# Sheet2.net
KiCad netlist of a schematic drawn in Altium Designer
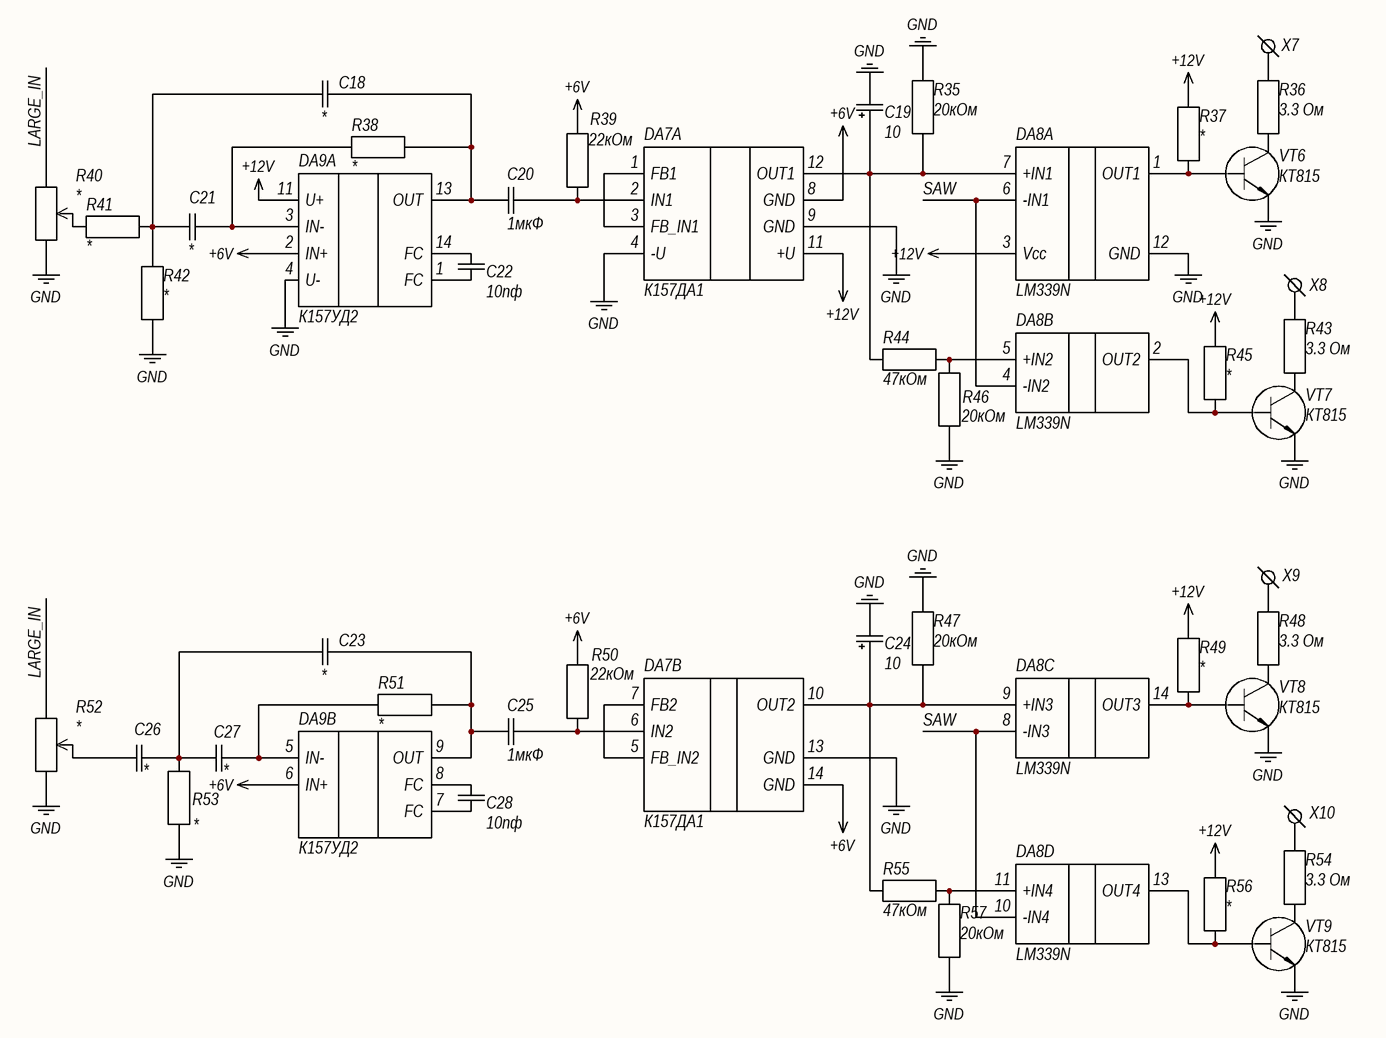
[diagram p0: Sheet2.SchDoc]

(export (version "E")
  (design (tool "Eeschema 10.0.6"))
  (components
    (comp (ref "C18") (value "*") (footprint "C 15mm") (libsource (lib "lib") (part "Capacitor")))
    (comp (ref "C19") (value "10") (footprint "C 3.5mm") (libsource (lib "lib") (part "Capacitor Pol")))
    (comp (ref "C20") (value "1мкФ") (footprint "C 10mm") (libsource (lib "lib") (part "Capacitor")))
    (comp (ref "C21") (value "*") (footprint "C 15mm") (libsource (lib "lib") (part "Capacitor")))
    (comp (ref "C22") (value "10пф") (footprint "C 10mm") (libsource (lib "lib") (part "Capacitor")))
    (comp (ref "C23") (value "*") (footprint "C 15mm") (libsource (lib "lib") (part "Capacitor")))
    (comp (ref "C24") (value "10") (footprint "C 3.5mm") (libsource (lib "lib") (part "Capacitor Pol")))
    (comp (ref "C25") (value "1мкФ") (footprint "C 10mm") (libsource (lib "lib") (part "Capacitor")))
    (comp (ref "C26") (value "*") (footprint "C 15mm") (libsource (lib "lib") (part "Capacitor")))
    (comp (ref "C27") (value "*") (footprint "C 15mm") (libsource (lib "lib") (part "Capacitor")))
    (comp (ref "C28") (value "10пф") (footprint "C 10mm") (libsource (lib "lib") (part "Capacitor")))
    (comp (ref "DA7") (value "К157ДА1") (footprint "14-LEAD DIP") (libsource (lib "lib") (part "К157ДА1")))
    (comp (ref "DA8") (value "LM339N") (footprint "14-LEAD DIP") (libsource (lib "lib") (part "LM339N")))
    (comp (ref "DA9") (value "К157УД2") (footprint "14-LEAD DIP") (libsource (lib "lib") (part "К157УД2")))
    (comp (ref "R35") (value "20кОм") (footprint "R 10mm") (libsource (lib "") (part "Resistor_1")))
    (comp (ref "R36") (value "3.3 Ом") (footprint "R 10mm") (libsource (lib "") (part "Resistor_1")))
    (comp (ref "R37") (value "*") (footprint "R 10mm") (libsource (lib "") (part "Resistor_1")))
    (comp (ref "R38") (value "*") (footprint "R 10mm") (libsource (lib "") (part "Resistor_2")))
    (comp (ref "R39") (value "22кОм") (footprint "R 10mm") (libsource (lib "") (part "Resistor_1")))
    (comp (ref "R40")
      (value "*")
      (footprint "OFF BOARD RESISTOR")
      (libsource (lib "lib") (part "ResistorVar"))
    )
    (comp (ref "R41") (value "*") (footprint "R 10mm") (libsource (lib "lib") (part "Resistor")))
    (comp (ref "R42") (value "*") (footprint "R 10mm") (libsource (lib "") (part "Resistor_1")))
    (comp (ref "R43") (value "3.3 Ом") (footprint "R 10mm") (libsource (lib "") (part "Resistor_1")))
    (comp (ref "R44") (value "47кОм") (footprint "R 10mm") (libsource (lib "lib") (part "Resistor")))
    (comp (ref "R45") (value "*") (footprint "R 10mm") (libsource (lib "") (part "Resistor_1")))
    (comp (ref "R46") (value "20кОм") (footprint "R 10mm") (libsource (lib "") (part "Resistor_1")))
    (comp (ref "R47") (value "20кОм") (footprint "R 10mm") (libsource (lib "") (part "Resistor_1")))
    (comp (ref "R48") (value "3.3 Ом") (footprint "R 10mm") (libsource (lib "") (part "Resistor_1")))
    (comp (ref "R49") (value "*") (footprint "R 10mm") (libsource (lib "") (part "Resistor_1")))
    (comp (ref "R50") (value "22кОм") (footprint "R 10mm") (libsource (lib "") (part "Resistor_1")))
    (comp (ref "R51") (value "*") (footprint "R 10mm") (libsource (lib "") (part "Resistor_2")))
    (comp (ref "R52")
      (value "*")
      (footprint "OFF BOARD RESISTOR")
      (libsource (lib "lib") (part "ResistorVar"))
    )
    (comp (ref "R53") (value "*") (footprint "R 10mm") (libsource (lib "") (part "Resistor_1")))
    (comp (ref "R54") (value "3.3 Ом") (footprint "R 10mm") (libsource (lib "") (part "Resistor_1")))
    (comp (ref "R55") (value "47кОм") (footprint "R 10mm") (libsource (lib "lib") (part "Resistor")))
    (comp (ref "R56") (value "*") (footprint "R 10mm") (libsource (lib "") (part "Resistor_1")))
    (comp (ref "R57") (value "20кОм") (footprint "R 10mm") (libsource (lib "") (part "Resistor_1")))
    (comp (ref "VT6")
      (value "КТ815")
      (footprint "KT-27")
      (description "Transistor")
      (libsource (lib "lib") (part "NPN"))
    )
    (comp (ref "VT7")
      (value "КТ815")
      (footprint "KT-27")
      (description "Transistor")
      (libsource (lib "lib") (part "NPN"))
    )
    (comp (ref "VT8")
      (value "КТ815")
      (footprint "KT-27")
      (description "Transistor")
      (libsource (lib "lib") (part "NPN"))
    )
    (comp (ref "VT9")
      (value "КТ815")
      (footprint "KT-27")
      (description "Transistor")
      (libsource (lib "lib") (part "NPN"))
    )
    (comp (ref "X7") (value "~") (footprint "TP 1,4mm") (libsource (lib "lib") (part "TP")))
    (comp (ref "X8") (value "~") (footprint "TP 1,4mm") (libsource (lib "lib") (part "TP")))
    (comp (ref "X9") (value "~") (footprint "TP 1,4mm") (libsource (lib "lib") (part "TP")))
    (comp (ref "X10") (value "~") (footprint "TP 1,4mm") (libsource (lib "lib") (part "TP")))
  )
  (nets
    (net (code "1") (name "+6V") (class "Default")
      (node (ref "DA7") (pin "14") (pinfunction "GND_14") (pintype "power_in"))
      (node (ref "DA7") (pin "8") (pinfunction "GND_8") (pintype "power_in"))
      (node (ref "DA9") (pin "2") (pinfunction "IN+_2") (pintype "power_in"))
      (node (ref "DA9") (pin "6") (pinfunction "IN+_6") (pintype "power_in"))
      (node (ref "R39") (pin "2") (pinfunction "2_2") (pintype "passive"))
      (node (ref "R50") (pin "2") (pinfunction "2_2") (pintype "passive"))
    )
    (net (code "2") (name "+12V") (class "Default")
      (node (ref "DA7") (pin "11") (pinfunction "+U_11") (pintype "power_in"))
      (node (ref "DA8") (pin "3") (pinfunction "Vcc_3") (pintype "power_in"))
      (node (ref "DA9") (pin "11") (pinfunction "U+_11") (pintype "power_in"))
      (node (ref "R37") (pin "2") (pinfunction "2_2") (pintype "passive"))
      (node (ref "R45") (pin "2") (pinfunction "2_2") (pintype "passive"))
      (node (ref "R49") (pin "2") (pinfunction "2_2") (pintype "passive"))
      (node (ref "R56") (pin "2") (pinfunction "2_2") (pintype "passive"))
    )
    (net (code "3") (name "/LARGE_IN") (class "Default")
      (node (ref "R40") (pin "1") (pinfunction "1_1") (pintype "passive"))
      (node (ref "R52") (pin "1") (pinfunction "1_1") (pintype "passive"))
    )
    (net (code "4") (name "/SAW") (class "Default")
      (node (ref "DA8") (pin "10") (pinfunction "-IN4_10") (pintype "power_in"))
      (node (ref "DA8") (pin "4") (pinfunction "-IN2_4") (pintype "power_in"))
      (node (ref "DA8") (pin "6") (pinfunction "-IN1_6") (pintype "power_in"))
      (node (ref "DA8") (pin "8") (pinfunction "-IN3_8") (pintype "power_in"))
    )
    (net (code "5") (name "GND") (class "Default")
      (node (ref "C19") (pin "2") (pinfunction "2_2") (pintype "passive"))
      (node (ref "C24") (pin "2") (pinfunction "2_2") (pintype "passive"))
      (node (ref "DA7") (pin "13") (pinfunction "GND_13") (pintype "power_in"))
      (node (ref "DA7") (pin "4") (pinfunction "-U_4") (pintype "power_in"))
      (node (ref "DA7") (pin "9") (pinfunction "GND_9") (pintype "power_in"))
      (node (ref "DA8") (pin "12") (pinfunction "GND_12") (pintype "power_in"))
      (node (ref "DA9") (pin "4") (pinfunction "U-_4") (pintype "power_in"))
      (node (ref "R35") (pin "2") (pinfunction "2_2") (pintype "passive"))
      (node (ref "R40") (pin "2") (pinfunction "2_2") (pintype "passive"))
      (node (ref "R42") (pin "1") (pinfunction "1_1") (pintype "passive"))
      (node (ref "R46") (pin "1") (pinfunction "1_1") (pintype "passive"))
      (node (ref "R47") (pin "2") (pinfunction "2_2") (pintype "passive"))
      (node (ref "R52") (pin "2") (pinfunction "2_2") (pintype "passive"))
      (node (ref "R53") (pin "1") (pinfunction "1_1") (pintype "passive"))
      (node (ref "R57") (pin "1") (pinfunction "1_1") (pintype "passive"))
      (node (ref "VT6") (pin "2") (pinfunction "2_2") (pintype "passive"))
      (node (ref "VT7") (pin "2") (pinfunction "2_2") (pintype "passive"))
      (node (ref "VT8") (pin "2") (pinfunction "2_2") (pintype "passive"))
      (node (ref "VT9") (pin "2") (pinfunction "2_2") (pintype "passive"))
    )
    (net (code "6") (name "Net-(C18-Pad1)") (class "Default")
      (node (ref "C18") (pin "1") (pinfunction "1_1") (pintype "passive"))
      (node (ref "C21") (pin "1") (pinfunction "1_1") (pintype "passive"))
      (node (ref "R41") (pin "2") (pinfunction "2_2") (pintype "passive"))
      (node (ref "R42") (pin "2") (pinfunction "2_2") (pintype "passive"))
    )
    (net (code "7") (name "Net-(C22-Pad1)") (class "Default")
      (node (ref "C22") (pin "1") (pinfunction "1_1") (pintype "passive"))
      (node (ref "DA9") (pin "1") (pinfunction "FC_1") (pintype "power_in"))
    )
    (net (code "8") (name "Net-(C22-Pad2)") (class "Default")
      (node (ref "C22") (pin "2") (pinfunction "2_2") (pintype "passive"))
      (node (ref "DA9") (pin "14") (pinfunction "FC_14") (pintype "power_in"))
    )
    (net (code "9") (name "Net-(C23-Pad1)") (class "Default")
      (node (ref "C23") (pin "1") (pinfunction "1_1") (pintype "passive"))
      (node (ref "C26") (pin "2") (pinfunction "2_2") (pintype "passive"))
      (node (ref "C27") (pin "1") (pinfunction "1_1") (pintype "passive"))
      (node (ref "R53") (pin "2") (pinfunction "2_2") (pintype "passive"))
    )
    (net (code "10") (name "Net-(C26-Pad1)") (class "Default")
      (node (ref "C26") (pin "1") (pinfunction "1_1") (pintype "passive"))
      (node (ref "R52") (pin "3") (pinfunction "3_3") (pintype "power_in"))
    )
    (net (code "11") (name "Net-(C28-Pad1)") (class "Default")
      (node (ref "C28") (pin "1") (pinfunction "1_1") (pintype "passive"))
      (node (ref "DA9") (pin "7") (pinfunction "FC_7") (pintype "power_in"))
    )
    (net (code "12") (name "Net-(C28-Pad2)") (class "Default")
      (node (ref "C28") (pin "2") (pinfunction "2_2") (pintype "passive"))
      (node (ref "DA9") (pin "8") (pinfunction "FC_8") (pintype "power_in"))
    )
    (net (code "13") (name "Net-(DA7A-FB1)") (class "Default")
      (node (ref "DA7") (pin "1") (pinfunction "FB1_1") (pintype "power_in"))
      (node (ref "DA7") (pin "3") (pinfunction "FB_IN1_3") (pintype "power_in"))
    )
    (net (code "14") (name "Net-(DA7A-IN1)") (class "Default")
      (node (ref "C20") (pin "2") (pinfunction "2_2") (pintype "passive"))
      (node (ref "DA7") (pin "2") (pinfunction "IN1_2") (pintype "power_in"))
      (node (ref "R39") (pin "1") (pinfunction "1_1") (pintype "passive"))
    )
    (net (code "15") (name "Net-(DA7A-OUT1)") (class "Default")
      (node (ref "C19") (pin "1") (pinfunction "1_1") (pintype "passive"))
      (node (ref "DA7") (pin "12") (pinfunction "OUT1_12") (pintype "power_in"))
      (node (ref "DA8") (pin "7") (pinfunction "+IN1_7") (pintype "power_in"))
      (node (ref "R35") (pin "1") (pinfunction "1_1") (pintype "passive"))
      (node (ref "R44") (pin "1") (pinfunction "1_1") (pintype "passive"))
    )
    (net (code "16") (name "Net-(DA7B-FB2)") (class "Default")
      (node (ref "DA7") (pin "5") (pinfunction "FB_IN2_5") (pintype "power_in"))
      (node (ref "DA7") (pin "7") (pinfunction "FB2_7") (pintype "power_in"))
    )
    (net (code "17") (name "Net-(DA7B-IN2)") (class "Default")
      (node (ref "C25") (pin "2") (pinfunction "2_2") (pintype "passive"))
      (node (ref "DA7") (pin "6") (pinfunction "IN2_6") (pintype "power_in"))
      (node (ref "R50") (pin "1") (pinfunction "1_1") (pintype "passive"))
    )
    (net (code "18") (name "Net-(DA7B-OUT2)") (class "Default")
      (node (ref "C24") (pin "1") (pinfunction "1_1") (pintype "passive"))
      (node (ref "DA7") (pin "10") (pinfunction "OUT2_10") (pintype "power_in"))
      (node (ref "DA8") (pin "9") (pinfunction "+IN3_9") (pintype "power_in"))
      (node (ref "R47") (pin "1") (pinfunction "1_1") (pintype "passive"))
      (node (ref "R55") (pin "1") (pinfunction "1_1") (pintype "passive"))
    )
    (net (code "19") (name "Net-(DA8A-OUT1)") (class "Default")
      (node (ref "DA8") (pin "1") (pinfunction "OUT1_1") (pintype "power_in"))
      (node (ref "R37") (pin "1") (pinfunction "1_1") (pintype "passive"))
      (node (ref "VT6") (pin "1") (pinfunction "1_1") (pintype "passive"))
    )
    (net (code "20") (name "Net-(DA8B-+IN2)") (class "Default")
      (node (ref "DA8") (pin "5") (pinfunction "+IN2_5") (pintype "power_in"))
      (node (ref "R44") (pin "2") (pinfunction "2_2") (pintype "passive"))
      (node (ref "R46") (pin "2") (pinfunction "2_2") (pintype "passive"))
    )
    (net (code "21") (name "Net-(DA8B-OUT2)") (class "Default")
      (node (ref "DA8") (pin "2") (pinfunction "OUT2_2") (pintype "power_in"))
      (node (ref "R45") (pin "1") (pinfunction "1_1") (pintype "passive"))
      (node (ref "VT7") (pin "1") (pinfunction "1_1") (pintype "passive"))
    )
    (net (code "22") (name "Net-(DA8C-OUT3)") (class "Default")
      (node (ref "DA8") (pin "14") (pinfunction "OUT3_14") (pintype "power_in"))
      (node (ref "R49") (pin "1") (pinfunction "1_1") (pintype "passive"))
      (node (ref "VT8") (pin "1") (pinfunction "1_1") (pintype "passive"))
    )
    (net (code "23") (name "Net-(DA8D-+IN4)") (class "Default")
      (node (ref "DA8") (pin "11") (pinfunction "+IN4_11") (pintype "power_in"))
      (node (ref "R55") (pin "2") (pinfunction "2_2") (pintype "passive"))
      (node (ref "R57") (pin "2") (pinfunction "2_2") (pintype "passive"))
    )
    (net (code "24") (name "Net-(DA8D-OUT4)") (class "Default")
      (node (ref "DA8") (pin "13") (pinfunction "OUT4_13") (pintype "power_in"))
      (node (ref "R56") (pin "1") (pinfunction "1_1") (pintype "passive"))
      (node (ref "VT9") (pin "1") (pinfunction "1_1") (pintype "passive"))
    )
    (net (code "25") (name "Net-(DA9A-IN-)") (class "Default")
      (node (ref "C21") (pin "2") (pinfunction "2_2") (pintype "passive"))
      (node (ref "DA9") (pin "3") (pinfunction "IN-_3") (pintype "power_in"))
      (node (ref "R38") (pin "2") (pinfunction "2_2") (pintype "passive"))
    )
    (net (code "26") (name "Net-(DA9A-OUT)") (class "Default")
      (node (ref "C18") (pin "2") (pinfunction "2_2") (pintype "passive"))
      (node (ref "C20") (pin "1") (pinfunction "1_1") (pintype "passive"))
      (node (ref "DA9") (pin "13") (pinfunction "OUT_13") (pintype "power_in"))
      (node (ref "R38") (pin "1") (pinfunction "1_1") (pintype "passive"))
    )
    (net (code "27") (name "Net-(DA9B-IN-)") (class "Default")
      (node (ref "C27") (pin "2") (pinfunction "2_2") (pintype "passive"))
      (node (ref "DA9") (pin "5") (pinfunction "IN-_5") (pintype "power_in"))
      (node (ref "R51") (pin "2") (pinfunction "2_2") (pintype "passive"))
    )
    (net (code "28") (name "Net-(DA9B-OUT)") (class "Default")
      (node (ref "C23") (pin "2") (pinfunction "2_2") (pintype "passive"))
      (node (ref "C25") (pin "1") (pinfunction "1_1") (pintype "passive"))
      (node (ref "DA9") (pin "9") (pinfunction "OUT_9") (pintype "power_in"))
      (node (ref "R51") (pin "1") (pinfunction "1_1") (pintype "passive"))
    )
    (net (code "29") (name "Net-(R36-Pad1)") (class "Default")
      (node (ref "R36") (pin "1") (pinfunction "1_1") (pintype "passive"))
      (node (ref "VT6") (pin "3") (pinfunction "3_3") (pintype "passive"))
    )
    (net (code "30") (name "Net-(R36-Pad2)") (class "Default")
      (node (ref "R36") (pin "2") (pinfunction "2_2") (pintype "passive"))
      (node (ref "X7") (pin "1") (pinfunction "1_1") (pintype "power_in"))
    )
    (net (code "31") (name "Net-(R40-Pad3)") (class "Default")
      (node (ref "R40") (pin "3") (pinfunction "3_3") (pintype "power_in"))
      (node (ref "R41") (pin "1") (pinfunction "1_1") (pintype "passive"))
    )
    (net (code "32") (name "Net-(R43-Pad1)") (class "Default")
      (node (ref "R43") (pin "1") (pinfunction "1_1") (pintype "passive"))
      (node (ref "VT7") (pin "3") (pinfunction "3_3") (pintype "passive"))
    )
    (net (code "33") (name "Net-(R43-Pad2)") (class "Default")
      (node (ref "R43") (pin "2") (pinfunction "2_2") (pintype "passive"))
      (node (ref "X8") (pin "1") (pinfunction "1_1") (pintype "power_in"))
    )
    (net (code "34") (name "Net-(R48-Pad1)") (class "Default")
      (node (ref "R48") (pin "1") (pinfunction "1_1") (pintype "passive"))
      (node (ref "VT8") (pin "3") (pinfunction "3_3") (pintype "passive"))
    )
    (net (code "35") (name "Net-(R48-Pad2)") (class "Default")
      (node (ref "R48") (pin "2") (pinfunction "2_2") (pintype "passive"))
      (node (ref "X9") (pin "1") (pinfunction "1_1") (pintype "power_in"))
    )
    (net (code "36") (name "Net-(R54-Pad1)") (class "Default")
      (node (ref "R54") (pin "1") (pinfunction "1_1") (pintype "passive"))
      (node (ref "VT9") (pin "3") (pinfunction "3_3") (pintype "passive"))
    )
    (net (code "37") (name "Net-(R54-Pad2)") (class "Default")
      (node (ref "R54") (pin "2") (pinfunction "2_2") (pintype "passive"))
      (node (ref "X10") (pin "1") (pinfunction "1_1") (pintype "power_in"))
    )
  )
)
